# FD-MGS-A.net
KiCad netlist of a schematic drawn in EasyEDA Pro
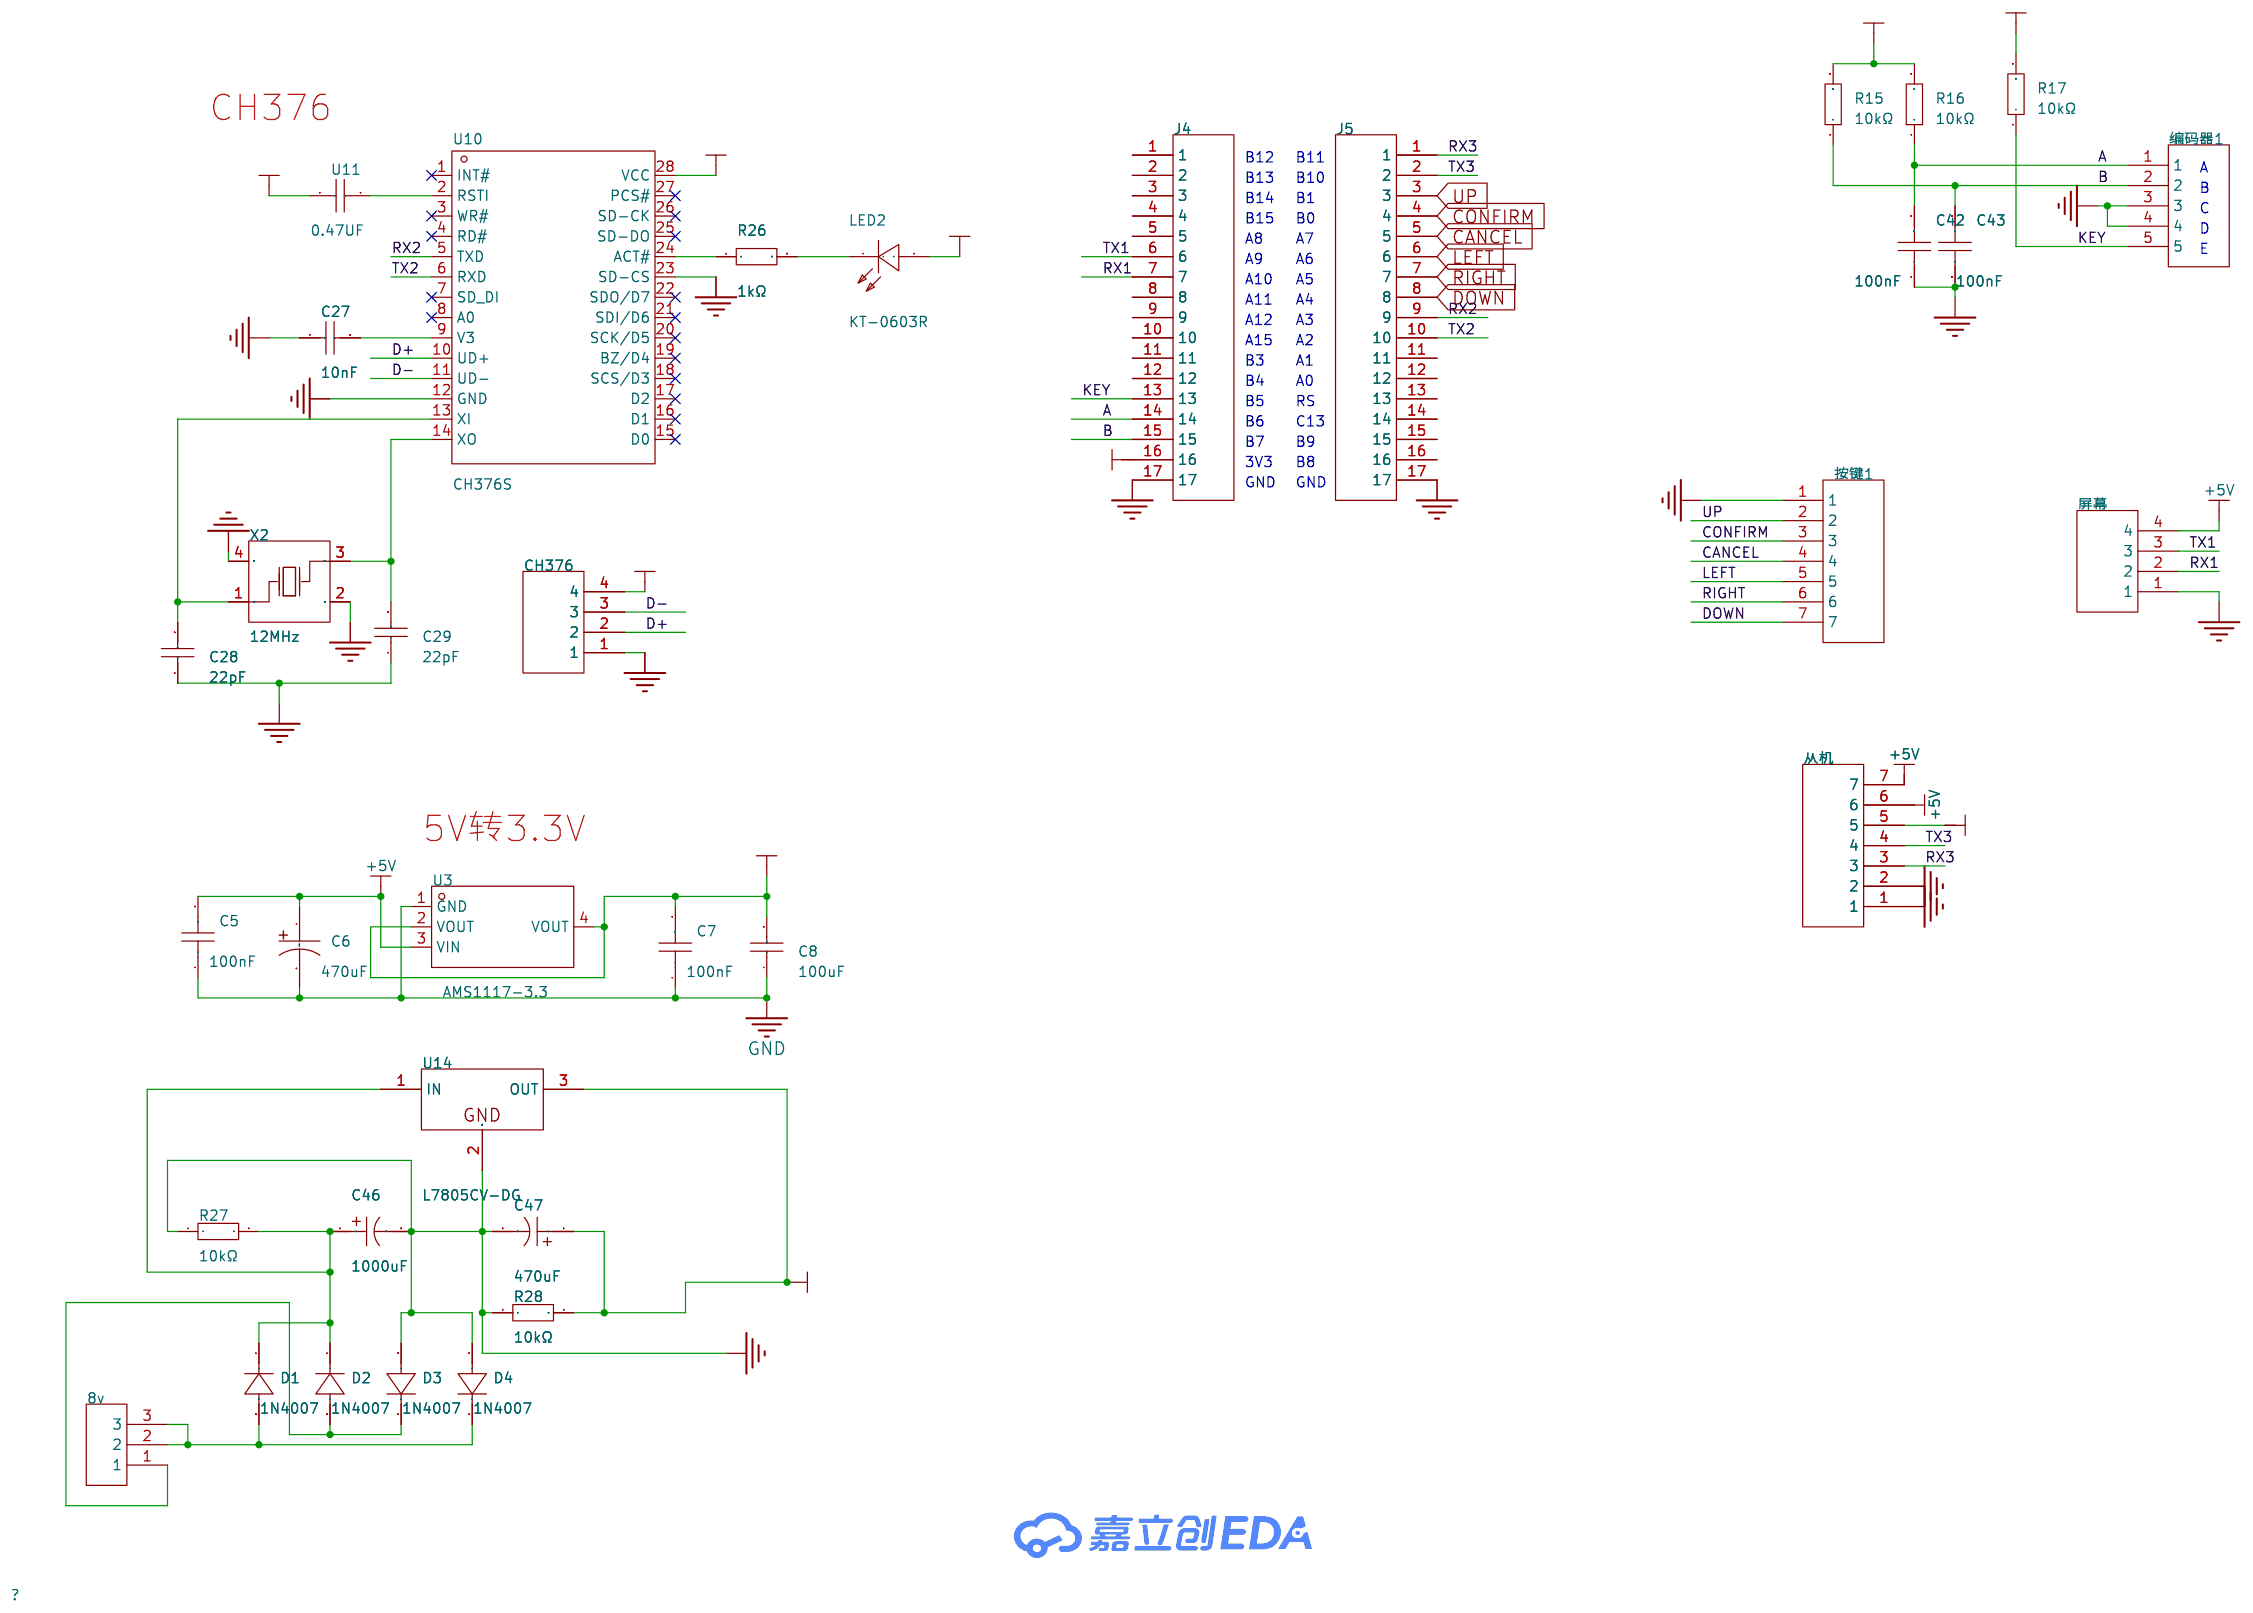
[diagram p0: schematic sheet]

(export (version "E")
  (design (tool "Eeschema 10.0.6"))
  (components
    (comp (ref "8v")
      (value "~")
      (footprint "easyedapro:CH2.54-3插座")
      (libsource (lib "easyedapro") (part "HDR-3P"))
    )
    (comp (ref "C5")
      (value "100nF")
      (footprint "easyedapro:C0603")
      (libsource (lib "easyedapro") (part "CapAcitance"))
    )
    (comp (ref "C6")
      (value "470uF")
      (footprint "easyedapro:CAP-SMD_BD6.3-L6.6-W6.6-FD")
      (description "容值:470uF;精度:±20%;额定电压:10V;纹波电流:200mA@120Hz;等效串联电阻:-;")
      (fields (field (name "Manufacturer Part") "RVT1A471M0607") (field (name "Manufacturer") "ROQANG(容强)"))
      (libsource (lib "easyedapro") (part "RVT1A471M0607_C335982"))
    )
    (comp (ref "C7")
      (value "100nF")
      (footprint "easyedapro:C0603")
      (libsource (lib "easyedapro") (part "CapAcitance"))
    )
    (comp (ref "C8")
      (value "100uF")
      (footprint "easyedapro:C1206")
      (description "容值:100uF;精度:±20%;额定电压:6.3V;材质(温度系数):X5R;")
      (fields
        (field (name "Manufacturer Part") "CL31A107MQHNNNE")
        (field (name "Manufacturer") "SAMSUNG(三星)")
      )
      (libsource (lib "easyedapro") (part "CL31A107MQHNNNE"))
    )
    (comp (ref "C27")
      (value "10nF")
      (footprint "easyedapro:C0603")
      (description "容值:10nF;精度:±10%;额定电压:50V;材质(温度系数):X7R;")
      (fields (field (name "Manufacturer Part") "0603B103K500NT") (field (name "Manufacturer") "FH(风华)"))
      (libsource (lib "easyedapro") (part "0603B103K500NT"))
    )
    (comp (ref "C28")
      (value "22pF")
      (footprint "easyedapro:C0603")
      (description "容值:22pF;精度:±5%;额定电压:50V;材质(温度系数):C0G;")
      (fields
        (field (name "Manufacturer Part") "CL10C220JB8NNNC")
        (field (name "Manufacturer") "SAMSUNG(三星)")
      )
      (libsource (lib "easyedapro") (part "CL10C220JB8NNNC"))
    )
    (comp (ref "C29")
      (value "22pF")
      (footprint "easyedapro:C0603")
      (description "容值:22pF;精度:±5%;额定电压:50V;材质(温度系数):C0G;")
      (fields
        (field (name "Manufacturer Part") "CL10C220JB8NNNC")
        (field (name "Manufacturer") "SAMSUNG(三星)")
      )
      (libsource (lib "easyedapro") (part "CL10C220JB8NNNC"))
    )
    (comp (ref "C42")
      (value "100nF")
      (footprint "easyedapro:C0402")
      (description "容值:100nF;精度:±10%;额定电压:50V;材质(温度系数):X7R;")
      (fields
        (field (name "Manufacturer Part") "CL05B104KB54PNC")
        (field (name "Manufacturer") "SAMSUNG(三星)")
      )
      (libsource (lib "easyedapro") (part "CL05B104KB54PNC"))
    )
    (comp (ref "C43")
      (value "100nF")
      (footprint "easyedapro:C0402")
      (description "容值:100nF;精度:±10%;额定电压:50V;材质(温度系数):X7R;")
      (fields
        (field (name "Manufacturer Part") "CL05B104KB54PNC")
        (field (name "Manufacturer") "SAMSUNG(三星)")
      )
      (libsource (lib "easyedapro") (part "CL05B104KB54PNC"))
    )
    (comp (ref "C46")
      (value "1000uF")
      (footprint "easyedapro:CAP-TH_BD10.0-P5.00-D0.6-FD")
      (description "容值:1000uF;额定电压:35V;")
      (fields
        (field (name "Manufacturer Part") "CD288108M1V1020VFL")
        (field (name "Manufacturer") "HRK(鸿瑞凯电子)")
      )
      (libsource (lib "easyedapro") (part "CD288108M1V1020VFL"))
    )
    (comp (ref "C47")
      (value "470uF")
      (footprint "easyedapro:CAP-TH_BD8.0-P3.50-D0.5-FD")
      (description "容值:470uF;精度:±20%;额定电压:16V;")
      (fields (field (name "Manufacturer Part") "16V470uF CD288") (field (name "Manufacturer") "HRK(鸿瑞凯电子)"))
      (libsource (lib "easyedapro") (part "16V470UF CD288"))
    )
    (comp (ref "CH376")
      (value "~")
      (footprint "easyedapro:CH2.54-4插座")
      (libsource (lib "easyedapro") (part "HDR-4P"))
    )
    (comp (ref "D1")
      (value "1N4007")
      (footprint "easyedapro:DO-41_BD2.4-L4.7-P8.70-D0.8-RD")
      (description "二极管配置:独立式;正向压降(Vf):1V@1A;直流反向耐压(Vr):1kV;整流电流:1A;")
      (fields (field (name "Manufacturer") "GOODWORK(固得沃克)"))
      (libsource (lib "easyedapro") (part "1N4007_C2985028"))
    )
    (comp (ref "D2")
      (value "1N4007")
      (footprint "easyedapro:DO-41_BD2.4-L4.7-P8.70-D0.8-RD")
      (description "二极管配置:独立式;正向压降(Vf):1V@1A;直流反向耐压(Vr):1kV;整流电流:1A;")
      (fields (field (name "Manufacturer") "GOODWORK(固得沃克)"))
      (libsource (lib "easyedapro") (part "1N4007_C2985028"))
    )
    (comp (ref "D3")
      (value "1N4007")
      (footprint "easyedapro:DO-41_BD2.4-L4.7-P8.70-D0.8-RD")
      (description "二极管配置:独立式;正向压降(Vf):1V@1A;直流反向耐压(Vr):1kV;整流电流:1A;")
      (fields (field (name "Manufacturer") "GOODWORK(固得沃克)"))
      (libsource (lib "easyedapro") (part "1N4007_C2985028"))
    )
    (comp (ref "D4")
      (value "1N4007")
      (footprint "easyedapro:DO-41_BD2.4-L4.7-P8.70-D0.8-RD")
      (description "二极管配置:独立式;正向压降(Vf):1V@1A;直流反向耐压(Vr):1kV;整流电流:1A;")
      (fields (field (name "Manufacturer") "GOODWORK(固得沃克)"))
      (libsource (lib "easyedapro") (part "1N4007_C2985028"))
    )
    (comp (ref "J4") (value "~") (libsource (lib "easyedapro") (part "HDR-17P")))
    (comp (ref "J5") (value "~") (libsource (lib "easyedapro") (part "HDR-17P")))
    (comp (ref "LED2")
      (value "KT-0603R")
      (footprint "easyedapro:LED0603-RD")
      (description "发光颜色:红色;功率:-;正向电流:-;主波长:-;二极管配置:-;透镜颜色:-;色温:-;发光角度:-;载带方式:-;工作温度:-40°C~+85°C;")
      (fields (field (name "Manufacturer") "KENTO"))
      (libsource (lib "easyedapro") (part "KT-0603R"))
    )
    (comp (ref "R15")
      (value "10kΩ")
      (footprint "easyedapro:R0805")
      (description "电阻类型:厚膜电阻;阻值:10kΩ;精度:±1%;功率:125mW;最大工作电压:150V;温度系数:±100ppm/°C;")
      (fields
        (field (name "Manufacturer Part") "0805W8F1002T5E")
        (field (name "Manufacturer") "UNI-ROYAL(厚声)")
      )
      (libsource (lib "easyedapro") (part "0805W8F1002T5E"))
    )
    (comp (ref "R16")
      (value "10kΩ")
      (footprint "easyedapro:R0805")
      (description "电阻类型:厚膜电阻;阻值:10kΩ;精度:±1%;功率:125mW;最大工作电压:150V;温度系数:±100ppm/°C;")
      (fields
        (field (name "Manufacturer Part") "0805W8F1002T5E")
        (field (name "Manufacturer") "UNI-ROYAL(厚声)")
      )
      (libsource (lib "easyedapro") (part "0805W8F1002T5E"))
    )
    (comp (ref "R17")
      (value "10kΩ")
      (footprint "easyedapro:R0805")
      (description "电阻类型:厚膜电阻;阻值:10kΩ;精度:±1%;功率:125mW;最大工作电压:150V;温度系数:±100ppm/°C;")
      (fields
        (field (name "Manufacturer Part") "0805W8F1002T5E")
        (field (name "Manufacturer") "UNI-ROYAL(厚声)")
      )
      (libsource (lib "easyedapro") (part "0805W8F1002T5E"))
    )
    (comp (ref "R26")
      (value "1kΩ")
      (footprint "easyedapro:R0603")
      (description "电阻类型:厚膜电阻;阻值:1kΩ;精度:±1%;功率:100mW;最大工作电压:75V;温度系数:±100ppm/°C;")
      (fields
        (field (name "Manufacturer Part") "0603WAF1001T5E")
        (field (name "Manufacturer") "UNI-ROYAL(厚声)")
      )
      (libsource (lib "easyedapro") (part "0603WAF1001T5E"))
    )
    (comp (ref "R27")
      (value "10kΩ")
      (footprint "easyedapro:Res_1/8W")
      (libsource (lib "easyedapro") (part "电阻"))
    )
    (comp (ref "R28")
      (value "10kΩ")
      (footprint "easyedapro:Res_1/8W")
      (libsource (lib "easyedapro") (part "电阻"))
    )
    (comp (ref "U3")
      (value "AMS1117-3.3")
      (footprint "easyedapro:SOT-223-3_L6.5-W3.4-P2.30-LS7.0-BR")
      (description "输出类型:固定;最大输入电压:-;输出电压:3.3V;最大输出电流:1A;电源纹波抑制比(PSRR):72dB@(120Hz);输出极性:正极;")
      (fields (field (name "Manufacturer") "AMS"))
      (libsource (lib "easyedapro") (part "AMS1117-3.3"))
    )
    (comp (ref "U10")
      (value "CH376S")
      (footprint "easyedapro:SOIC-28_L17.9-W7.5-P1.27-LS10.3-BL")
      (description "应用功能:-;接口协议:USB 2.0;数据速率:12Mbps;")
      (fields (field (name "Manufacturer") "WCH(南京沁恒)"))
      (libsource (lib "easyedapro") (part "CH376S"))
    )
    (comp (ref "U11")
      (value "0.47UF")
      (footprint "easyedapro:C0603")
      (libsource (lib "easyedapro") (part "CAPCER0.47UF25VX7R0603"))
    )
    (comp (ref "U14")
      (value "L7805CV-DG")
      (footprint "easyedapro:TO-220-3_L10.0-W4.5-P2.54-L")
      (description "输出类型:固定;最大输入电压:35V;输出电压:5V;输出电流:1.5A;电源纹波抑制比(PSRR):62dB@(120Hz);输出极性:正极;")
      (fields (field (name "Manufacturer") "ST(意法半导体)"))
      (libsource (lib "easyedapro") (part "L7805CV-DG"))
    )
    (comp (ref "X2")
      (value "12MHz")
      (footprint "easyedapro:CRYSTAL-SMD_4P-L3.2-W2.5-BL")
      (description "晶振类型:贴片晶振;频率:12MHz;常温频差:±10ppm;外接负载电容:20pF;频率稳定度(全温):±20ppm;")
      (fields (field (name "Manufacturer Part") "X322512MSB4SI") (field (name "Manufacturer") "YXC(扬兴晶振)"))
      (libsource (lib "easyedapro") (part "X322512MSB4SI"))
    )
    (comp (ref "从机")
      (value "~")
      (footprint "easyedapro:CH2.54-7插座")
      (libsource (lib "easyedapro") (part "HDR-7P"))
    )
    (comp (ref "屏幕")
      (value "~")
      (footprint "easyedapro:CH2.54-4插座")
      (libsource (lib "easyedapro") (part "HDR-4P"))
    )
    (comp (ref "按键1")
      (value "~")
      (footprint "easyedapro:CH2.54-7插座")
      (libsource (lib "easyedapro") (part "HDR-7P"))
    )
    (comp (ref "编码器1")
      (value "~")
      (footprint "easyedapro:CH2.54-5插座")
      (libsource (lib "easyedapro") (part "HDR-5P"))
    )
  )
  (nets
    (net (code "1") (name "+3V3") (class "Default")
      (node (ref "C7") (pin "2") (pinfunction "2_2") (pintype "input"))
      (node (ref "C8") (pin "2") (pinfunction "2_2") (pintype "input"))
      (node (ref "J4") (pin "16") (pinfunction "16_16") (pintype "input"))
      (node (ref "LED2") (pin "2") (pinfunction "A_2") (pintype "unspecified"))
      (node (ref "R15") (pin "2") (pinfunction "2_2") (pintype "input"))
      (node (ref "R16") (pin "2") (pinfunction "2_2") (pintype "input"))
      (node (ref "R17") (pin "2") (pinfunction "2_2") (pintype "input"))
      (node (ref "U10") (pin "28") (pinfunction "VCC_28") (pintype "unspecified"))
      (node (ref "U11") (pin "1") (pinfunction "1_1") (pintype "input"))
      (node (ref "U3") (pin "2") (pinfunction "VOUT_2") (pintype "unspecified"))
      (node (ref "U3") (pin "4") (pinfunction "VOUT_4") (pintype "unspecified"))
      (node (ref "从机") (pin "5") (pinfunction "5_5") (pintype "input"))
    )
    (net (code "2") (name "+5V") (class "Default")
      (node (ref "C47") (pin "1") (pinfunction "1_1") (pintype "input"))
      (node (ref "C5") (pin "2") (pinfunction "2_2") (pintype "input"))
      (node (ref "C6") (pin "1") (pinfunction "1_1") (pintype "unspecified"))
      (node (ref "CH376") (pin "4") (pinfunction "4_4") (pintype "input"))
      (node (ref "R28") (pin "2") (pinfunction "2_2") (pintype "input"))
      (node (ref "U14") (pin "3") (pinfunction "OUT_3") (pintype "unspecified"))
      (node (ref "U3") (pin "3") (pinfunction "VIN_3") (pintype "unspecified"))
      (node (ref "从机") (pin "6") (pinfunction "6_6") (pintype "input"))
      (node (ref "从机") (pin "7") (pinfunction "7_7") (pintype "input"))
      (node (ref "屏幕") (pin "4") (pinfunction "4_4") (pintype "input"))
    )
    (net (code "3") (name "/A") (class "Default")
      (node (ref "C42") (pin "2") (pinfunction "2_2") (pintype "input"))
      (node (ref "J4") (pin "14") (pinfunction "14_14") (pintype "input"))
      (node (ref "R16") (pin "1") (pinfunction "1_1") (pintype "input"))
      (node (ref "编码器1") (pin "1") (pinfunction "1_1") (pintype "input"))
    )
    (net (code "4") (name "/B") (class "Default")
      (node (ref "C43") (pin "2") (pinfunction "2_2") (pintype "input"))
      (node (ref "J4") (pin "15") (pinfunction "15_15") (pintype "input"))
      (node (ref "R15") (pin "1") (pinfunction "1_1") (pintype "input"))
      (node (ref "编码器1") (pin "2") (pinfunction "2_2") (pintype "input"))
    )
    (net (code "5") (name "/D+") (class "Default")
      (node (ref "CH376") (pin "2") (pinfunction "2_2") (pintype "input"))
      (node (ref "U10") (pin "10") (pinfunction "UD+_10") (pintype "unspecified"))
    )
    (net (code "6") (name "/D-") (class "Default")
      (node (ref "CH376") (pin "3") (pinfunction "3_3") (pintype "input"))
      (node (ref "U10") (pin "11") (pinfunction "UD-_11") (pintype "unspecified"))
    )
    (net (code "7") (name "/KEY") (class "Default")
      (node (ref "J4") (pin "13") (pinfunction "13_13") (pintype "input"))
      (node (ref "R17") (pin "1") (pinfunction "1_1") (pintype "input"))
      (node (ref "编码器1") (pin "5") (pinfunction "5_5") (pintype "input"))
    )
    (net (code "8") (name "/RX1") (class "Default")
      (node (ref "J4") (pin "7") (pinfunction "7_7") (pintype "input"))
      (node (ref "屏幕") (pin "2") (pinfunction "2_2") (pintype "input"))
    )
    (net (code "9") (name "/RX2") (class "Default")
      (node (ref "J5") (pin "9") (pinfunction "9_9") (pintype "input"))
      (node (ref "U10") (pin "5") (pinfunction "TXD_5") (pintype "unspecified"))
    )
    (net (code "10") (name "/RX3") (class "Default")
      (node (ref "J5") (pin "1") (pinfunction "1_1") (pintype "input"))
      (node (ref "从机") (pin "3") (pinfunction "3_3") (pintype "input"))
    )
    (net (code "11") (name "/TX1") (class "Default")
      (node (ref "J4") (pin "6") (pinfunction "6_6") (pintype "input"))
      (node (ref "屏幕") (pin "3") (pinfunction "3_3") (pintype "input"))
    )
    (net (code "12") (name "/TX2") (class "Default")
      (node (ref "J5") (pin "10") (pinfunction "10_10") (pintype "input"))
      (node (ref "U10") (pin "6") (pinfunction "RXD_6") (pintype "unspecified"))
    )
    (net (code "13") (name "/TX3") (class "Default")
      (node (ref "J5") (pin "2") (pinfunction "2_2") (pintype "input"))
      (node (ref "从机") (pin "4") (pinfunction "4_4") (pintype "input"))
    )
    (net (code "14") (name "CANCEL") (class "Default")
      (node (ref "J5") (pin "5") (pinfunction "5_5") (pintype "input"))
      (node (ref "按键1") (pin "4") (pinfunction "4_4") (pintype "input"))
    )
    (net (code "15") (name "CONFIRM") (class "Default")
      (node (ref "J5") (pin "4") (pinfunction "4_4") (pintype "input"))
      (node (ref "按键1") (pin "3") (pinfunction "3_3") (pintype "input"))
    )
    (net (code "16") (name "DOWN") (class "Default")
      (node (ref "J5") (pin "8") (pinfunction "8_8") (pintype "input"))
      (node (ref "按键1") (pin "7") (pinfunction "7_7") (pintype "input"))
    )
    (net (code "17") (name "GND") (class "Default")
      (node (ref "C27") (pin "1") (pinfunction "1_1") (pintype "input"))
      (node (ref "C28") (pin "1") (pinfunction "1_1") (pintype "input"))
      (node (ref "C29") (pin "1") (pinfunction "1_1") (pintype "input"))
      (node (ref "C42") (pin "1") (pinfunction "1_1") (pintype "input"))
      (node (ref "C43") (pin "1") (pinfunction "1_1") (pintype "input"))
      (node (ref "C46") (pin "2") (pinfunction "2_2") (pintype "input"))
      (node (ref "C47") (pin "2") (pinfunction "2_2") (pintype "input"))
      (node (ref "C5") (pin "1") (pinfunction "1_1") (pintype "input"))
      (node (ref "C6") (pin "2") (pinfunction "2_2") (pintype "unspecified"))
      (node (ref "C7") (pin "1") (pinfunction "1_1") (pintype "input"))
      (node (ref "C8") (pin "1") (pinfunction "1_1") (pintype "input"))
      (node (ref "CH376") (pin "1") (pinfunction "1_1") (pintype "input"))
      (node (ref "D3") (pin "2") (pinfunction "A_2") (pintype "unspecified"))
      (node (ref "D4") (pin "2") (pinfunction "A_2") (pintype "unspecified"))
      (node (ref "J4") (pin "17") (pinfunction "17_17") (pintype "input"))
      (node (ref "J5") (pin "17") (pinfunction "17_17") (pintype "input"))
      (node (ref "R27") (pin "1") (pinfunction "1_1") (pintype "input"))
      (node (ref "R28") (pin "1") (pinfunction "1_1") (pintype "input"))
      (node (ref "U10") (pin "12") (pinfunction "GND_12") (pintype "unspecified"))
      (node (ref "U10") (pin "23") (pinfunction "SD-CS_23") (pintype "unspecified"))
      (node (ref "U14") (pin "2") (pinfunction "GND_2") (pintype "unspecified"))
      (node (ref "U3") (pin "1") (pinfunction "GND_1") (pintype "unspecified"))
      (node (ref "X2") (pin "2") (pinfunction "GND_2") (pintype "unspecified"))
      (node (ref "X2") (pin "4") (pinfunction "GND_4") (pintype "unspecified"))
      (node (ref "从机") (pin "1") (pinfunction "1_1") (pintype "input"))
      (node (ref "从机") (pin "2") (pinfunction "2_2") (pintype "input"))
      (node (ref "屏幕") (pin "1") (pinfunction "1_1") (pintype "input"))
      (node (ref "按键1") (pin "1") (pinfunction "1_1") (pintype "input"))
      (node (ref "编码器1") (pin "3") (pinfunction "3_3") (pintype "input"))
      (node (ref "编码器1") (pin "4") (pinfunction "4_4") (pintype "input"))
    )
    (net (code "18") (name "LEFT") (class "Default")
      (node (ref "J5") (pin "6") (pinfunction "6_6") (pintype "input"))
      (node (ref "按键1") (pin "5") (pinfunction "5_5") (pintype "input"))
    )
    (net (code "19") (name "Net-(D1-A)") (class "Default")
      (node (ref "8v") (pin "2") (pinfunction "2_2") (pintype "input"))
      (node (ref "8v") (pin "3") (pinfunction "3_3") (pintype "input"))
      (node (ref "D1") (pin "2") (pinfunction "A_2") (pintype "unspecified"))
      (node (ref "D4") (pin "1") (pinfunction "K_1") (pintype "unspecified"))
    )
    (net (code "20") (name "Net-(D1-K)") (class "Default")
      (node (ref "C46") (pin "1") (pinfunction "1_1") (pintype "input"))
      (node (ref "D1") (pin "1") (pinfunction "K_1") (pintype "unspecified"))
      (node (ref "D2") (pin "1") (pinfunction "K_1") (pintype "unspecified"))
      (node (ref "R27") (pin "2") (pinfunction "2_2") (pintype "input"))
      (node (ref "U14") (pin "1") (pinfunction "IN_1") (pintype "unspecified"))
    )
    (net (code "21") (name "Net-(D2-A)") (class "Default")
      (node (ref "8v") (pin "1") (pinfunction "1_1") (pintype "input"))
      (node (ref "D2") (pin "2") (pinfunction "A_2") (pintype "unspecified"))
      (node (ref "D3") (pin "1") (pinfunction "K_1") (pintype "unspecified"))
    )
    (net (code "22") (name "Net-(LED2-K)") (class "Default")
      (node (ref "LED2") (pin "1") (pinfunction "K_1") (pintype "unspecified"))
      (node (ref "R26") (pin "2") (pinfunction "2_2") (pintype "input"))
    )
    (net (code "23") (name "Net-(U10-ACT#)") (class "Default")
      (node (ref "R26") (pin "1") (pinfunction "1_1") (pintype "input"))
      (node (ref "U10") (pin "24") (pinfunction "ACT#_24") (pintype "unspecified"))
    )
    (net (code "24") (name "Net-(U10-RSTI)") (class "Default")
      (node (ref "U10") (pin "2") (pinfunction "RSTI_2") (pintype "unspecified"))
      (node (ref "U11") (pin "2") (pinfunction "2_2") (pintype "input"))
    )
    (net (code "25") (name "Net-(U10-V3)") (class "Default")
      (node (ref "C27") (pin "2") (pinfunction "2_2") (pintype "input"))
      (node (ref "U10") (pin "9") (pinfunction "V3_9") (pintype "unspecified"))
    )
    (net (code "26") (name "Net-(U10-XI)") (class "Default")
      (node (ref "C28") (pin "2") (pinfunction "2_2") (pintype "input"))
      (node (ref "U10") (pin "13") (pinfunction "XI_13") (pintype "unspecified"))
      (node (ref "X2") (pin "1") (pinfunction "OSC1_1") (pintype "unspecified"))
    )
    (net (code "27") (name "Net-(U10-XO)") (class "Default")
      (node (ref "C29") (pin "2") (pinfunction "2_2") (pintype "input"))
      (node (ref "U10") (pin "14") (pinfunction "XO_14") (pintype "unspecified"))
      (node (ref "X2") (pin "3") (pinfunction "OSC2_3") (pintype "unspecified"))
    )
    (net (code "28") (name "RIGHT") (class "Default")
      (node (ref "J5") (pin "7") (pinfunction "7_7") (pintype "input"))
      (node (ref "按键1") (pin "6") (pinfunction "6_6") (pintype "input"))
    )
    (net (code "29") (name "UP") (class "Default")
      (node (ref "J5") (pin "3") (pinfunction "3_3") (pintype "input"))
      (node (ref "按键1") (pin "2") (pinfunction "2_2") (pintype "input"))
    )
    (net (code "30") (name "unconnected-(J4-Pad1)") (class "Default")
      (node (ref "J4") (pin "1") (pinfunction "1_1") (pintype "input"))
    )
    (net (code "31") (name "unconnected-(J4-Pad2)") (class "Default")
      (node (ref "J4") (pin "2") (pinfunction "2_2") (pintype "input"))
    )
    (net (code "32") (name "unconnected-(J4-Pad3)") (class "Default")
      (node (ref "J4") (pin "3") (pinfunction "3_3") (pintype "input"))
    )
    (net (code "33") (name "unconnected-(J4-Pad4)") (class "Default")
      (node (ref "J4") (pin "4") (pinfunction "4_4") (pintype "input"))
    )
    (net (code "34") (name "unconnected-(J4-Pad5)") (class "Default")
      (node (ref "J4") (pin "5") (pinfunction "5_5") (pintype "input"))
    )
    (net (code "35") (name "unconnected-(J4-Pad8)") (class "Default")
      (node (ref "J4") (pin "8") (pinfunction "8_8") (pintype "input"))
    )
    (net (code "36") (name "unconnected-(J4-Pad9)") (class "Default")
      (node (ref "J4") (pin "9") (pinfunction "9_9") (pintype "input"))
    )
    (net (code "37") (name "unconnected-(J4-Pad10)") (class "Default")
      (node (ref "J4") (pin "10") (pinfunction "10_10") (pintype "input"))
    )
    (net (code "38") (name "unconnected-(J4-Pad11)") (class "Default")
      (node (ref "J4") (pin "11") (pinfunction "11_11") (pintype "input"))
    )
    (net (code "39") (name "unconnected-(J4-Pad12)") (class "Default")
      (node (ref "J4") (pin "12") (pinfunction "12_12") (pintype "input"))
    )
    (net (code "40") (name "unconnected-(J5-Pad11)") (class "Default")
      (node (ref "J5") (pin "11") (pinfunction "11_11") (pintype "input"))
    )
    (net (code "41") (name "unconnected-(J5-Pad12)") (class "Default")
      (node (ref "J5") (pin "12") (pinfunction "12_12") (pintype "input"))
    )
    (net (code "42") (name "unconnected-(J5-Pad13)") (class "Default")
      (node (ref "J5") (pin "13") (pinfunction "13_13") (pintype "input"))
    )
    (net (code "43") (name "unconnected-(J5-Pad14)") (class "Default")
      (node (ref "J5") (pin "14") (pinfunction "14_14") (pintype "input"))
    )
    (net (code "44") (name "unconnected-(J5-Pad15)") (class "Default")
      (node (ref "J5") (pin "15") (pinfunction "15_15") (pintype "input"))
    )
    (net (code "45") (name "unconnected-(J5-Pad16)") (class "Default")
      (node (ref "J5") (pin "16") (pinfunction "16_16") (pintype "input"))
    )
    (net (code "46") (name "unconnected-(U10-A0-Pad8)") (class "Default")
      (node (ref "U10") (pin "8") (pinfunction "A0_8") (pintype "unspecified+no_connect"))
    )
    (net (code "47") (name "unconnected-(U10-BZ{slash}D4-Pad19)") (class "Default")
      (node (ref "U10") (pin "19") (pinfunction "BZ/D4_19") (pintype "unspecified+no_connect"))
    )
    (net (code "48") (name "unconnected-(U10-D0-Pad15)") (class "Default")
      (node (ref "U10") (pin "15") (pinfunction "D0_15") (pintype "unspecified+no_connect"))
    )
    (net (code "49") (name "unconnected-(U10-D1-Pad16)") (class "Default")
      (node (ref "U10") (pin "16") (pinfunction "D1_16") (pintype "unspecified+no_connect"))
    )
    (net (code "50") (name "unconnected-(U10-D2-Pad17)") (class "Default")
      (node (ref "U10") (pin "17") (pinfunction "D2_17") (pintype "unspecified+no_connect"))
    )
    (net (code "51") (name "unconnected-(U10-INT#-Pad1)") (class "Default")
      (node (ref "U10") (pin "1") (pinfunction "INT#_1") (pintype "unspecified+no_connect"))
    )
    (net (code "52") (name "unconnected-(U10-PCS#-Pad27)") (class "Default")
      (node (ref "U10") (pin "27") (pinfunction "PCS#_27") (pintype "unspecified+no_connect"))
    )
    (net (code "53") (name "unconnected-(U10-RD#-Pad4)") (class "Default")
      (node (ref "U10") (pin "4") (pinfunction "RD#_4") (pintype "unspecified+no_connect"))
    )
    (net (code "54") (name "unconnected-(U10-SCK{slash}D5-Pad20)") (class "Default")
      (node (ref "U10") (pin "20") (pinfunction "SCK/D5_20") (pintype "unspecified+no_connect"))
    )
    (net (code "55") (name "unconnected-(U10-SCS{slash}D3-Pad18)") (class "Default")
      (node (ref "U10") (pin "18") (pinfunction "SCS/D3_18") (pintype "unspecified+no_connect"))
    )
    (net (code "56") (name "unconnected-(U10-SD-CK-Pad26)") (class "Default")
      (node (ref "U10") (pin "26") (pinfunction "SD-CK_26") (pintype "unspecified+no_connect"))
    )
    (net (code "57") (name "unconnected-(U10-SD-DO-Pad25)") (class "Default")
      (node (ref "U10") (pin "25") (pinfunction "SD-DO_25") (pintype "unspecified+no_connect"))
    )
    (net (code "58") (name "unconnected-(U10-SDI{slash}D6-Pad21)") (class "Default")
      (node (ref "U10") (pin "21") (pinfunction "SDI/D6_21") (pintype "unspecified+no_connect"))
    )
    (net (code "59") (name "unconnected-(U10-SDO{slash}D7-Pad22)") (class "Default")
      (node (ref "U10") (pin "22") (pinfunction "SDO/D7_22") (pintype "unspecified+no_connect"))
    )
    (net (code "60") (name "unconnected-(U10-SD_DI-Pad7)") (class "Default")
      (node (ref "U10") (pin "7") (pinfunction "SD_DI_7") (pintype "unspecified+no_connect"))
    )
    (net (code "61") (name "unconnected-(U10-WR#-Pad3)") (class "Default")
      (node (ref "U10") (pin "3") (pinfunction "WR#_3") (pintype "unspecified+no_connect"))
    )
  )
)
